# ESP_Grow_Main_Rev_A.net
KiCad netlist of a schematic drawn in Altium Designer
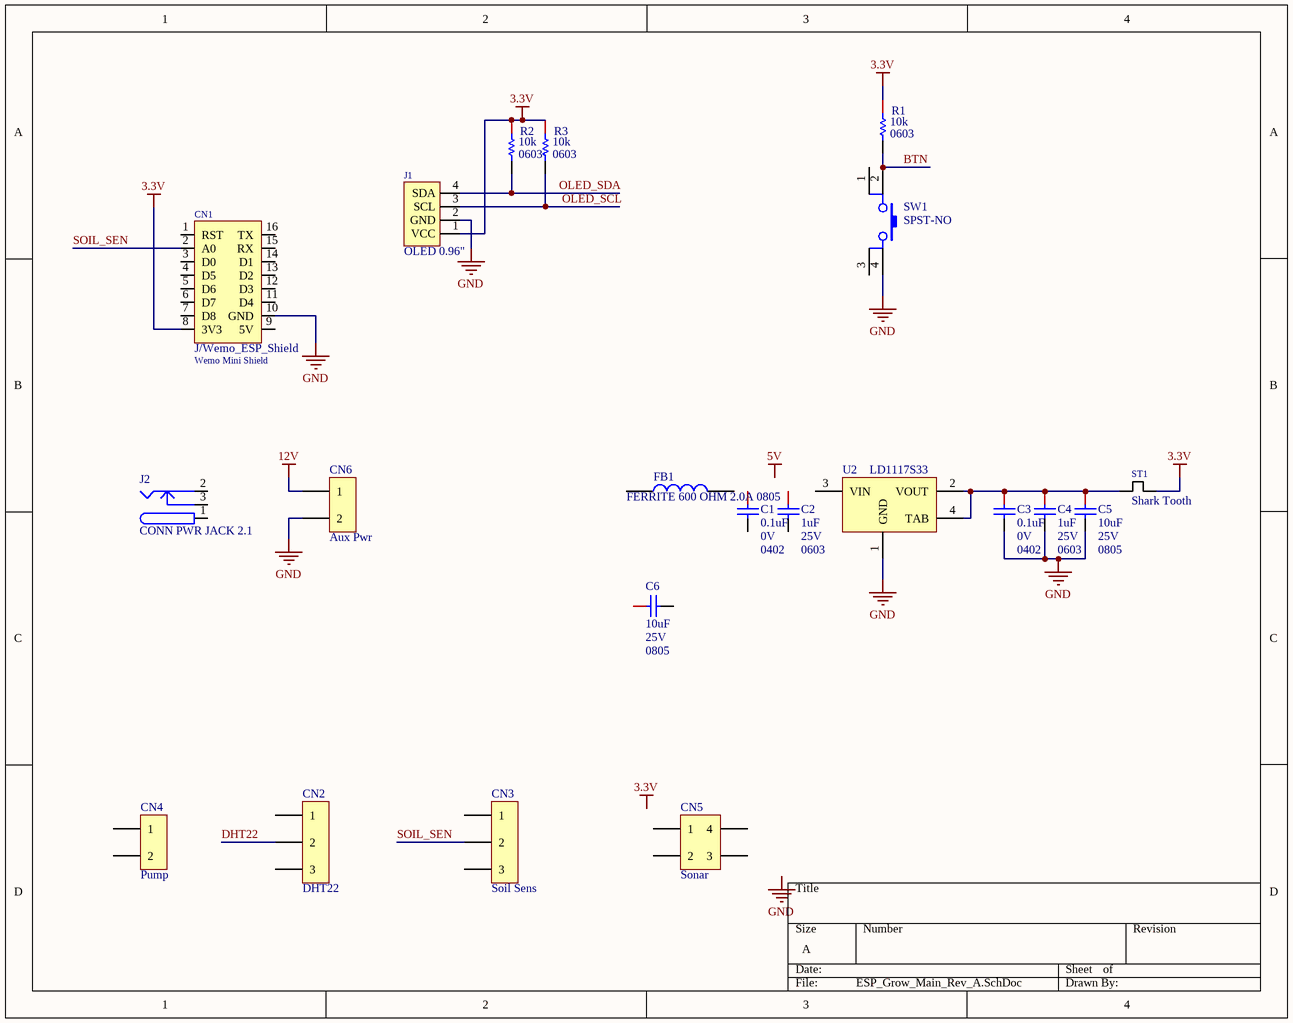
[diagram p0: ESP_Grow_Main_Rev_A.SchDoc]

(export (version "E")
  (design (tool "Eeschema 10.0.6"))
  (components
    (comp (ref "C1")
      (value "0.1uF")
      (footprint "CAPC0402(1005)_M")
      (description "CAP CER 0.1UF 50V X7R 0402")
      (fields
        (field (name "VOLTAGE (RATED)") "0V")
        (field (name "PACKAGE (IMPERIAL)") "0402")
        (field (name "TOLERANCE") "20%")
      )
      (libsource (lib "OLogic Nexus Vault") (part "=Capacitance"))
    )
    (comp (ref "C2")
      (value "1uF")
      (footprint "CAPC0603(1608)_N")
      (description "CAP CER 1UF 25V 10% X7R 0603")
      (fields
        (field (name "VOLTAGE (RATED)") "25V")
        (field (name "PACKAGE (IMPERIAL)") "0603")
        (field (name "TOLERANCE") "10%")
      )
      (libsource (lib "OLogic Nexus Vault") (part "=Capacitance"))
    )
    (comp (ref "C3")
      (value "0.1uF")
      (footprint "CAPC0402(1005)_M")
      (description "CAP CER 0.1UF 50V X7R 0402")
      (fields
        (field (name "VOLTAGE (RATED)") "0V")
        (field (name "PACKAGE (IMPERIAL)") "0402")
        (field (name "TOLERANCE") "20%")
      )
      (libsource (lib "OLogic Nexus Vault") (part "=Capacitance"))
    )
    (comp (ref "C4")
      (value "1uF")
      (footprint "CAPC0603(1608)_N")
      (description "CAP CER 1UF 25V 10% X7R 0603")
      (fields
        (field (name "VOLTAGE (RATED)") "25V")
        (field (name "PACKAGE (IMPERIAL)") "0603")
        (field (name "TOLERANCE") "10%")
      )
      (libsource (lib "OLogic Nexus Vault") (part "=Capacitance"))
    )
    (comp (ref "C5")
      (value "10uF")
      (footprint "CAPC0805(2012)_L")
      (description "CAP CER 10UF 25V X6S 0805")
      (fields
        (field (name "VOLTAGE (RATED)") "25V")
        (field (name "PACKAGE (IMPERIAL)") "0805")
        (field (name "TOLERANCE") "20%")
      )
      (libsource (lib "OLogic Nexus Vault") (part "=Capacitance"))
    )
    (comp (ref "C6")
      (value "10uF")
      (footprint "CAPC0805(2012)_L")
      (description "CAP CER 10UF 25V X6S 0805")
      (fields
        (field (name "VOLTAGE (RATED)") "25V")
        (field (name "PACKAGE (IMPERIAL)") "0805")
        (field (name "TOLERANCE") "20%")
      )
      (libsource (lib "OLogic Nexus Vault") (part "=Capacitance"))
    )
    (comp (ref "CN1")
      (value "J/Wemo_ESP_Shield")
      (footprint "Wemos_d1")
      (description "Wemo Mini Shield for ESP-12")
      (fields (field (name "NAME") "Wemo Mini Shield"))
      (libsource (lib "Kyle_Lib_04-20-19") (part "J/Wemo_ESP_Shield"))
    )
    (comp (ref "CN2")
      (value "DHT22")
      (footprint "Molex 1x3 Microfit 90deg")
      (description "Molex Microfit 1x3 90deg Header")
      (fields
        (field (name "MANUFACTURER") "Molex Inc")
        (field (name "MANUFACTURER PART NUMBER") "0436500304")
      )
      (libsource (lib "ologic-library_2018-09-22") (part "CMP-001-0428-01"))
    )
    (comp (ref "CN3")
      (value "Soil Sens")
      (footprint "Molex 1x3 Microfit 90deg")
      (description "Molex Microfit 1x3 90deg Header")
      (fields
        (field (name "MANUFACTURER") "Molex Inc")
        (field (name "MANUFACTURER PART NUMBER") "0436500304")
      )
      (libsource (lib "ologic-library_2018-09-22") (part "CMP-001-0428-01"))
    )
    (comp (ref "CN4")
      (value "Pump")
      (footprint "Molex 1x2 Microfit 90deg")
      (description "Molex Microfit 1x2 90deg Header")
      (fields (field (name "MANUFACTURER") "Molex") (field (name "MANUFACTURER PART NUMBER") "43650-0204"))
      (libsource (lib "ologic-library_2018-09-22") (part "CMP-001-0425-01"))
    )
    (comp (ref "CN5")
      (value "Sonar")
      (footprint "Molex 2x2 Microfit 90deg")
      (description "Molex Microfit 2x2 90deg Header")
      (fields
        (field (name "MANUFACTURER") "Molex Inc")
        (field (name "MANUFACTURER PART NUMBER") "0430450400")
      )
      (libsource (lib "ologic-library_2018-09-22") (part "CMP-001-0429-01"))
    )
    (comp (ref "CN6")
      (value "Aux Pwr")
      (footprint "Molex 1x2 Microfit 3.0")
      (description "Molex Microfit 1x2 Vert Header")
      (fields
        (field (name "MANUFACTURER PART NUMBER") "0430450227")
        (field (name "MANUFACTURER") "Molex, LLC")
      )
      (libsource (lib "OLogic Nexus Vault") (part "MICROFIT 3.0 HDR VERT CPI 2CKT"))
    )
    (comp (ref "FB1")
      (value "FERRITE 600 OHM 2.0A 0805")
      (footprint "RESC0805(2012)_N")
      (description "600 OHM 0805 2.0A")
      (fields
        (field (name "MANUFACTURER PART NUMBER") "742792040")
        (field (name "MANUFACTURER") "Wurth Electronics Inc")
        (field (name "CREATOR") "osman")
      )
      (libsource (lib "OLogic Nexus Vault") (part "FERRITE 600 OHM 2.0A 0805"))
    )
    (comp (ref "J1")
      (value "OLED 0.96\"")
      (footprint "OLED_0.96_I2C")
      (description "SSD1306 I2C OLED 0.96\"")
      (libsource (lib "Kyle_Lib_04-20-19") (part "OLED_0.96_I2C"))
    )
    (comp (ref "J2")
      (value "CONN PWR JACK 2.1")
      (footprint "CONN_PWR_JACK_2.1x5.5mm")
      (description "2.1 mm barrel jack")
      (fields
        (field (name "MANUFACTURER PART NUMBER") "PJ-002A")
        (field (name "MANUFACTURER") "CUI Inc")
        (field (name "PUBLISHER") "Altium Limited")
      )
      (libsource (lib "OLogic Nexus Vault") (part "CONN PWR JACK 2.1"))
    )
    (comp (ref "R1")
      (value "10K")
      (footprint "RESC0603(1608)_M")
      (description "RES 10K OHM 1/10W 1% 0603 SMD")
      (fields
        (field (name "PACKAGE (IMPERIAL)") "0603")
        (field (name "RESISTANCE") "10k")
        (field (name "POWER") "100mW")
        (field (name "TOLERANCE") "1%")
      )
      (libsource (lib "OLogic Nexus Vault") (part "=Resistance"))
    )
    (comp (ref "R2")
      (value "10K")
      (footprint "RESC0603(1608)_M")
      (description "RES 10K OHM 1/10W 1% 0603 SMD")
      (fields
        (field (name "PACKAGE (IMPERIAL)") "0603")
        (field (name "RESISTANCE") "10k")
        (field (name "POWER") "100mW")
        (field (name "TOLERANCE") "1%")
      )
      (libsource (lib "OLogic Nexus Vault") (part "=Resistance"))
    )
    (comp (ref "R3")
      (value "10K")
      (footprint "RESC0603(1608)_M")
      (description "RES 10K OHM 1/10W 1% 0603 SMD")
      (fields
        (field (name "PACKAGE (IMPERIAL)") "0603")
        (field (name "RESISTANCE") "10k")
        (field (name "POWER") "100mW")
        (field (name "TOLERANCE") "1%")
      )
      (libsource (lib "OLogic Nexus Vault") (part "=Resistance"))
    )
    (comp (ref "ST1")
      (value "Shark Tooth")
      (footprint "SharkTooth")
      (description "Sharks Tooth Small")
      (libsource (lib "Kyle_Lib_04-20-19") (part "Shark Tooth"))
    )
    (comp (ref "SW1")
      (value "PTS645SM43SMTR92 LFS")
      (footprint "SW TACT Red 6mm x 6mm")
      (description "SWITCH TACTILE SPST-NO 0.05A 12V")
      (fields (field (name "CIRCUIT") "SPST-NO") (field (name "MANUFACTURER") "C&K"))
      (libsource (lib "OLogic Nexus Vault") (part "PTS645SM43SMTR92 LFS"))
    )
    (comp (ref "U2")
      (value "LD1117S33")
      (footprint "DSO-G3")
      (description "3.3 volt fixed regulator, 800mA")
      (libsource (lib "OLogic Nexus Vault") (part "LD1117S33"))
    )
  )
  (nets
    (net (code "1") (name "/BTN") (class "Default")
      (node (ref "R1") (pin "2") (pinfunction "2_2") (pintype "passive"))
      (node (ref "SW1") (pin "2") (pinfunction "2_2") (pintype "passive"))
    )
    (net (code "2") (name "/DHT22") (class "Default")
      (node (ref "CN2") (pin "2") (pinfunction "2_2") (pintype "passive"))
    )
    (net (code "3") (name "/OLED_SCL") (class "Default")
      (node (ref "J1") (pin "3") (pinfunction "SCL_3") (pintype "passive"))
      (node (ref "R3") (pin "2") (pinfunction "2_2") (pintype "passive"))
    )
    (net (code "4") (name "/OLED_SDA") (class "Default")
      (node (ref "J1") (pin "4") (pinfunction "SDA_4") (pintype "passive"))
      (node (ref "R2") (pin "2") (pinfunction "2_2") (pintype "passive"))
    )
    (net (code "5") (name "/SOIL_SEN") (class "Default")
      (node (ref "CN1") (pin "2") (pinfunction "A0_2") (pintype "power_in"))
      (node (ref "CN3") (pin "2") (pinfunction "2_2") (pintype "passive"))
    )
    (net (code "6") (name "3.3V") (class "Default")
      (node (ref "CN1") (pin "8") (pinfunction "3V3_8") (pintype "power_in"))
      (node (ref "J1") (pin "1") (pinfunction "VCC_1") (pintype "passive"))
      (node (ref "R1") (pin "1") (pinfunction "1_1") (pintype "passive"))
      (node (ref "R2") (pin "1") (pinfunction "1_1") (pintype "passive"))
      (node (ref "R3") (pin "1") (pinfunction "1_1") (pintype "passive"))
      (node (ref "ST1") (pin "2") (pinfunction "2_2") (pintype "power_in"))
    )
    (net (code "8") (name "12V") (class "Default")
      (node (ref "CN6") (pin "1") (pinfunction "1_1") (pintype "passive"))
    )
    (net (code "9") (name "GND") (class "Default")
      (node (ref "C3") (pin "2") (pinfunction "2_2") (pintype "passive"))
      (node (ref "C4") (pin "2") (pinfunction "2_2") (pintype "passive"))
      (node (ref "C5") (pin "2") (pinfunction "2_2") (pintype "passive"))
      (node (ref "CN1") (pin "10") (pinfunction "GND_10") (pintype "power_in"))
      (node (ref "CN6") (pin "2") (pinfunction "2_2") (pintype "passive"))
      (node (ref "J1") (pin "2") (pinfunction "GND_2") (pintype "passive"))
      (node (ref "SW1") (pin "4") (pinfunction "4_4") (pintype "passive"))
      (node (ref "U2") (pin "1") (pinfunction "GND_1") (pintype "power_in"))
    )
    (net (code "10") (name "Net-(U2-TAB)") (class "Default")
      (node (ref "C3") (pin "1") (pinfunction "1_1") (pintype "passive"))
      (node (ref "C4") (pin "1") (pinfunction "1_1") (pintype "passive"))
      (node (ref "C5") (pin "1") (pinfunction "1_1") (pintype "passive"))
      (node (ref "ST1") (pin "1") (pinfunction "1_1") (pintype "power_in"))
      (node (ref "U2") (pin "2") (pinfunction "VOUT_2") (pintype "power_in"))
      (node (ref "U2") (pin "4") (pinfunction "TAB_4") (pintype "power_in"))
    )
    (net (code "11") (name "unconnected-(C1-Pad1)") (class "Default")
      (node (ref "C1") (pin "1") (pinfunction "1_1") (pintype "passive"))
    )
    (net (code "12") (name "unconnected-(C1-Pad2)") (class "Default")
      (node (ref "C1") (pin "2") (pinfunction "2_2") (pintype "passive"))
    )
    (net (code "13") (name "unconnected-(C2-Pad1)") (class "Default")
      (node (ref "C2") (pin "1") (pinfunction "1_1") (pintype "passive"))
    )
    (net (code "14") (name "unconnected-(C2-Pad2)") (class "Default")
      (node (ref "C2") (pin "2") (pinfunction "2_2") (pintype "passive"))
    )
    (net (code "15") (name "unconnected-(C6-Pad1)") (class "Default")
      (node (ref "C6") (pin "1") (pinfunction "1_1") (pintype "passive"))
    )
    (net (code "16") (name "unconnected-(C6-Pad2)") (class "Default")
      (node (ref "C6") (pin "2") (pinfunction "2_2") (pintype "passive"))
    )
    (net (code "17") (name "unconnected-(CN1-5V-Pad9)") (class "Default")
      (node (ref "CN1") (pin "9") (pinfunction "5V_9") (pintype "power_in"))
    )
    (net (code "18") (name "unconnected-(CN1-D0-Pad3)") (class "Default")
      (node (ref "CN1") (pin "3") (pinfunction "D0_3") (pintype "power_in"))
    )
    (net (code "19") (name "unconnected-(CN1-D1-Pad14)") (class "Default")
      (node (ref "CN1") (pin "14") (pinfunction "D1_14") (pintype "power_in"))
    )
    (net (code "20") (name "unconnected-(CN1-D2-Pad13)") (class "Default")
      (node (ref "CN1") (pin "13") (pinfunction "D2_13") (pintype "power_in"))
    )
    (net (code "21") (name "unconnected-(CN1-D3-Pad12)") (class "Default")
      (node (ref "CN1") (pin "12") (pinfunction "D3_12") (pintype "power_in"))
    )
    (net (code "22") (name "unconnected-(CN1-D4-Pad11)") (class "Default")
      (node (ref "CN1") (pin "11") (pinfunction "D4_11") (pintype "power_in"))
    )
    (net (code "23") (name "unconnected-(CN1-D5-Pad4)") (class "Default")
      (node (ref "CN1") (pin "4") (pinfunction "D5_4") (pintype "power_in"))
    )
    (net (code "24") (name "unconnected-(CN1-D6-Pad5)") (class "Default")
      (node (ref "CN1") (pin "5") (pinfunction "D6_5") (pintype "power_in"))
    )
    (net (code "25") (name "unconnected-(CN1-D7-Pad6)") (class "Default")
      (node (ref "CN1") (pin "6") (pinfunction "D7_6") (pintype "power_in"))
    )
    (net (code "26") (name "unconnected-(CN1-D8-Pad7)") (class "Default")
      (node (ref "CN1") (pin "7") (pinfunction "D8_7") (pintype "power_in"))
    )
    (net (code "27") (name "unconnected-(CN1-RST-Pad1)") (class "Default")
      (node (ref "CN1") (pin "1") (pinfunction "RST_1") (pintype "power_in"))
    )
    (net (code "28") (name "unconnected-(CN1-RX-Pad15)") (class "Default")
      (node (ref "CN1") (pin "15") (pinfunction "RX_15") (pintype "power_in"))
    )
    (net (code "29") (name "unconnected-(CN1-TX-Pad16)") (class "Default")
      (node (ref "CN1") (pin "16") (pinfunction "TX_16") (pintype "power_in"))
    )
    (net (code "30") (name "unconnected-(CN2-Pad1)") (class "Default")
      (node (ref "CN2") (pin "1") (pinfunction "1_1") (pintype "passive"))
    )
    (net (code "31") (name "unconnected-(CN2-Pad3)") (class "Default")
      (node (ref "CN2") (pin "3") (pinfunction "3_3") (pintype "passive"))
    )
    (net (code "32") (name "unconnected-(CN3-Pad1)") (class "Default")
      (node (ref "CN3") (pin "1") (pinfunction "1_1") (pintype "passive"))
    )
    (net (code "33") (name "unconnected-(CN3-Pad3)") (class "Default")
      (node (ref "CN3") (pin "3") (pinfunction "3_3") (pintype "passive"))
    )
    (net (code "34") (name "unconnected-(CN4-Pad1)") (class "Default")
      (node (ref "CN4") (pin "1") (pinfunction "1_1") (pintype "passive"))
    )
    (net (code "35") (name "unconnected-(CN4-Pad2)") (class "Default")
      (node (ref "CN4") (pin "2") (pinfunction "2_2") (pintype "passive"))
    )
    (net (code "36") (name "unconnected-(CN5-Pad1)") (class "Default")
      (node (ref "CN5") (pin "1") (pinfunction "1_1") (pintype "passive"))
    )
    (net (code "37") (name "unconnected-(CN5-Pad2)") (class "Default")
      (node (ref "CN5") (pin "2") (pinfunction "2_2") (pintype "passive"))
    )
    (net (code "38") (name "unconnected-(CN5-Pad3)") (class "Default")
      (node (ref "CN5") (pin "3") (pinfunction "3_3") (pintype "passive"))
    )
    (net (code "39") (name "unconnected-(CN5-Pad4)") (class "Default")
      (node (ref "CN5") (pin "4") (pinfunction "4_4") (pintype "passive"))
    )
    (net (code "40") (name "unconnected-(FB1-Pad1)") (class "Default")
      (node (ref "FB1") (pin "1") (pinfunction "1_1") (pintype "passive"))
    )
    (net (code "41") (name "unconnected-(FB1-Pad2)") (class "Default")
      (node (ref "FB1") (pin "2") (pinfunction "2_2") (pintype "passive"))
    )
    (net (code "42") (name "unconnected-(J2-Pad1)") (class "Default")
      (node (ref "J2") (pin "1") (pinfunction "1_1") (pintype "power_in"))
    )
    (net (code "43") (name "unconnected-(J2-Pad2)") (class "Default")
      (node (ref "J2") (pin "2") (pinfunction "2_2") (pintype "power_in"))
    )
    (net (code "44") (name "unconnected-(J2-Pad3)") (class "Default")
      (node (ref "J2") (pin "3") (pinfunction "3_3") (pintype "power_in"))
    )
    (net (code "45") (name "unconnected-(SW1-Pad1)") (class "Default")
      (node (ref "SW1") (pin "1") (pinfunction "1_1") (pintype "passive"))
    )
    (net (code "46") (name "unconnected-(SW1-Pad3)") (class "Default")
      (node (ref "SW1") (pin "3") (pinfunction "3_3") (pintype "passive"))
    )
    (net (code "47") (name "unconnected-(U2-VIN-Pad3)") (class "Default")
      (node (ref "U2") (pin "3") (pinfunction "VIN_3") (pintype "power_in"))
    )
  )
)
